# untitled.net
KiCad netlist of a schematic drawn in EAGLE
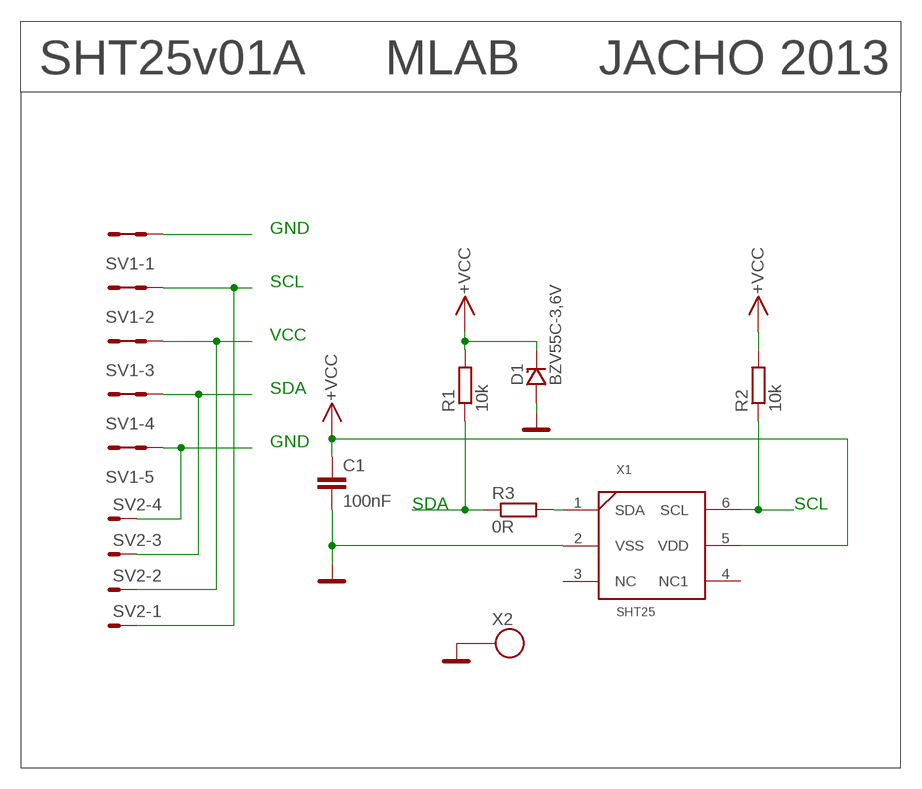
[diagram p0: schematic, sheet 1]

(export (version "E")
  (design (tool "Eeschema 10.0.6"))
  (components
    (comp (ref "C1")
      (value "100nF")
      (footprint "eagle-import:C0805")
      (libsource (lib "eagle-import") (part "C-EUC0805"))
    )
    (comp (ref "D1")
      (value "BZV55C-3,6V")
      (footprint "eagle-import:MINIMELF")
      (libsource (lib "eagle-import") (part "D-ZENEROVA"))
    )
    (comp (ref "R1")
      (value "10k")
      (footprint "eagle-import:R0805")
      (libsource (lib "eagle-import") (part "R-EU_R0805"))
    )
    (comp (ref "R2")
      (value "10k")
      (footprint "eagle-import:R0805")
      (libsource (lib "eagle-import") (part "R-EU_R0805"))
    )
    (comp (ref "R3")
      (value "0R")
      (footprint "eagle-import:R0805")
      (libsource (lib "eagle-import") (part "R-EU_R0805"))
    )
    (comp (ref "SV1")
      (value "MA05-2")
      (footprint "eagle-import:MA05-2")
      (libsource (lib "eagle-import") (part "MA05-2"))
    )
    (comp (ref "SV2")
      (value "SMD_MA04-01")
      (footprint "eagle-import:SMD_MA04-1")
      (libsource (lib "eagle-import") (part "SMD_MA04-01"))
    )
    (comp (ref "X1")
      (value "SHT25")
      (footprint "eagle-import:SHT25")
      (libsource (lib "eagle-import") (part "SHT25"))
    )
    (comp (ref "X2")
      (value "SROUB3M")
      (footprint "eagle-import:SROUB3M")
      (libsource (lib "eagle-import") (part "SROUB3M"))
    )
  )
  (nets
    (net (code "1") (name "+VCC") (class "Default")
      (node (ref "C1") (pin "1") (pinfunction "1_1") (pintype "passive"))
      (node (ref "D1") (pin "C") (pinfunction "K_C") (pintype "passive"))
      (node (ref "R1") (pin "2") (pinfunction "2_2") (pintype "passive"))
      (node (ref "R2") (pin "2") (pinfunction "2_2") (pintype "passive"))
      (node (ref "SV1") (pin "5") (pinfunction "K_5") (pintype "passive"))
      (node (ref "SV1") (pin "6") (pinfunction "K_6") (pintype "passive"))
      (node (ref "SV2") (pin "2") (pinfunction "P$1_2") (pintype "passive"))
      (node (ref "X1") (pin "5") (pinfunction "VDD_5") (pintype "bidirectional"))
    )
    (net (code "2") (name "/SCL") (class "Default")
      (node (ref "R2") (pin "1") (pinfunction "1_1") (pintype "passive"))
      (node (ref "SV1") (pin "3") (pinfunction "K_3") (pintype "passive"))
      (node (ref "SV1") (pin "4") (pinfunction "K_4") (pintype "passive"))
      (node (ref "SV2") (pin "1") (pinfunction "P$1_1") (pintype "passive"))
      (node (ref "X1") (pin "6") (pinfunction "SCL_6") (pintype "bidirectional"))
    )
    (net (code "3") (name "/SDA") (class "Default")
      (node (ref "R1") (pin "1") (pinfunction "1_1") (pintype "passive"))
      (node (ref "R3") (pin "1") (pinfunction "1_1") (pintype "passive"))
      (node (ref "SV1") (pin "7") (pinfunction "K_7") (pintype "passive"))
      (node (ref "SV1") (pin "8") (pinfunction "K_8") (pintype "passive"))
      (node (ref "SV2") (pin "3") (pinfunction "P$1_3") (pintype "passive"))
    )
    (net (code "4") (name "GND") (class "Default")
      (node (ref "C1") (pin "2") (pinfunction "2_2") (pintype "passive"))
      (node (ref "D1") (pin "A") (pinfunction "A_A") (pintype "passive"))
      (node (ref "SV1") (pin "1") (pinfunction "K_1") (pintype "passive"))
      (node (ref "SV1") (pin "10") (pinfunction "K_10") (pintype "passive"))
      (node (ref "SV1") (pin "2") (pinfunction "K_2") (pintype "passive"))
      (node (ref "SV1") (pin "9") (pinfunction "K_9") (pintype "passive"))
      (node (ref "SV2") (pin "4") (pinfunction "P$1_4") (pintype "passive"))
      (node (ref "X1") (pin "2") (pinfunction "VSS_2") (pintype "bidirectional"))
      (node (ref "X2") (pin "P$1") (pinfunction "P$1_P$1") (pintype "bidirectional"))
    )
    (net (code "5") (name "Net-(X1-SDA)") (class "Default")
      (node (ref "R3") (pin "2") (pinfunction "2_2") (pintype "passive"))
      (node (ref "X1") (pin "1") (pinfunction "SDA_1") (pintype "bidirectional"))
    )
    (net (code "6") (name "unconnected-(X1-NC-Pad3)") (class "Default")
      (node (ref "X1") (pin "3") (pinfunction "NC_3") (pintype "bidirectional"))
    )
    (net (code "7") (name "unconnected-(X1-NC1-Pad4)") (class "Default")
      (node (ref "X1") (pin "4") (pinfunction "NC1_4") (pintype "bidirectional"))
    )
  )
)
